# bno055.net
KiCad netlist of a schematic drawn in EAGLE
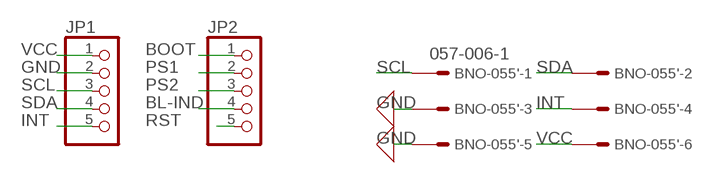
[diagram p0: schematic, sheet 1]

(export (version "E")
  (design (tool "Eeschema 10.0.6"))
  (components
    (comp (ref "BNO-055'")
      (value "057-006-1")
      (footprint "eagle-import:057-006-1")
      (libsource (lib "eagle-import") (part "057-006-1"))
    )
    (comp (ref "JP1")
      (value "PINHD-1X5")
      (footprint "eagle-import:1X05")
      (libsource (lib "eagle-import") (part "PINHD-1X5"))
    )
    (comp (ref "JP2")
      (value "PINHD-1X5")
      (footprint "eagle-import:1X05")
      (libsource (lib "eagle-import") (part "PINHD-1X5"))
    )
  )
  (nets
    (net (code "1") (name "/BL-IND") (class "Default")
      (node (ref "JP2") (pin "4") (pinfunction "4_4") (pintype "passive"))
    )
    (net (code "2") (name "/BOOT") (class "Default")
      (node (ref "JP2") (pin "1") (pinfunction "1_1") (pintype "passive"))
    )
    (net (code "3") (name "/INT") (class "Default")
      (node (ref "BNO-055'") (pin "4") (pinfunction "S_4") (pintype "passive"))
      (node (ref "JP1") (pin "5") (pinfunction "5_5") (pintype "passive"))
    )
    (net (code "4") (name "/PS1") (class "Default")
      (node (ref "JP2") (pin "2") (pinfunction "2_2") (pintype "passive"))
    )
    (net (code "5") (name "/PS2") (class "Default")
      (node (ref "JP2") (pin "3") (pinfunction "3_3") (pintype "passive"))
    )
    (net (code "6") (name "/RST") (class "Default")
      (node (ref "JP2") (pin "5") (pinfunction "5_5") (pintype "passive"))
    )
    (net (code "7") (name "/SCL") (class "Default")
      (node (ref "BNO-055'") (pin "1") (pinfunction "S_1") (pintype "passive"))
      (node (ref "JP1") (pin "3") (pinfunction "3_3") (pintype "passive"))
    )
    (net (code "8") (name "/SDA") (class "Default")
      (node (ref "BNO-055'") (pin "2") (pinfunction "S_2") (pintype "passive"))
      (node (ref "JP1") (pin "4") (pinfunction "4_4") (pintype "passive"))
    )
    (net (code "9") (name "/VCC") (class "Default")
      (node (ref "BNO-055'") (pin "6") (pinfunction "S_6") (pintype "passive"))
      (node (ref "JP1") (pin "1") (pinfunction "1_1") (pintype "passive"))
    )
    (net (code "10") (name "GND") (class "Default")
      (node (ref "BNO-055'") (pin "3") (pinfunction "S_3") (pintype "passive"))
      (node (ref "BNO-055'") (pin "5") (pinfunction "S_5") (pintype "passive"))
      (node (ref "JP1") (pin "2") (pinfunction "2_2") (pintype "passive"))
    )
  )
)
